# ColorControl.net
KiCad netlist of a schematic drawn in EAGLE
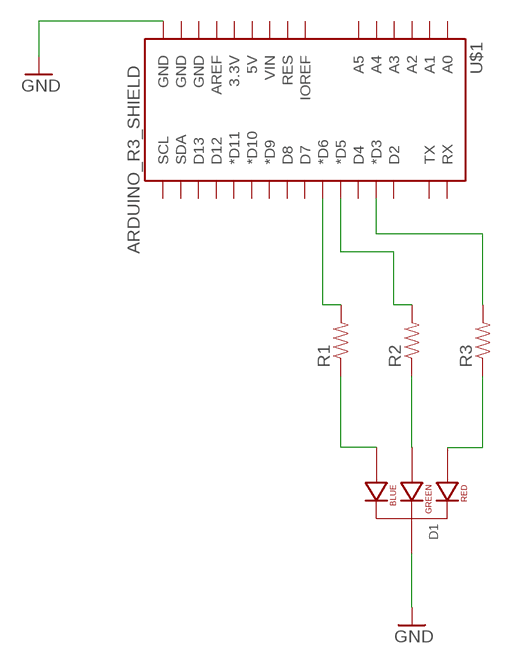
[diagram p0: schematic, sheet 1]

(export (version "E")
  (design (tool "Eeschema 10.0.6"))
  (components
    (comp (ref "D1")
      (value "LED-RGB-CC-THRUCLEAR")
      (footprint "eagle-import:LED-RGB-THRU")
      (libsource (lib "eagle-import") (part "LED-RGB-CC-THRUCLEAR"))
    )
    (comp (ref "R1")
      (value "RESISTORAXIAL-0.3")
      (footprint "eagle-import:AXIAL-0.3")
      (libsource (lib "eagle-import") (part "RESISTORAXIAL-0.3"))
    )
    (comp (ref "R2")
      (value "RESISTORAXIAL-0.3")
      (footprint "eagle-import:AXIAL-0.3")
      (libsource (lib "eagle-import") (part "RESISTORAXIAL-0.3"))
    )
    (comp (ref "R3")
      (value "RESISTORAXIAL-0.3")
      (footprint "eagle-import:AXIAL-0.3")
      (libsource (lib "eagle-import") (part "RESISTORAXIAL-0.3"))
    )
    (comp (ref "U$1")
      (value "ARDUINO_R3_SHIELD")
      (footprint "eagle-import:UNO_R3_SHIELD")
      (libsource (lib "eagle-import") (part "ARDUINO_R3_SHIELD"))
    )
  )
  (nets
    (net (code "1") (name "GND") (class "Default")
      (node (ref "D1") (pin "2") (pinfunction "CATHODE_2") (pintype "bidirectional"))
      (node (ref "U$1") (pin "GND@0") (pinfunction "GND_GND@0") (pintype "bidirectional"))
    )
    (net (code "2") (name "Net-(D1-BLUE_CATHODE)") (class "Default")
      (node (ref "D1") (pin "4") (pinfunction "BLUE_CATHODE_4") (pintype "bidirectional"))
      (node (ref "R1") (pin "P$1") (pinfunction "1_P$1") (pintype "passive"))
    )
    (net (code "3") (name "Net-(D1-GREEN_CATHODE)") (class "Default")
      (node (ref "D1") (pin "3") (pinfunction "GREEN_CATHODE_3") (pintype "bidirectional"))
      (node (ref "R2") (pin "P$1") (pinfunction "1_P$1") (pintype "passive"))
    )
    (net (code "4") (name "Net-(D1-RED_CATHODE)") (class "Default")
      (node (ref "D1") (pin "1") (pinfunction "RED_CATHODE_1") (pintype "bidirectional"))
      (node (ref "R3") (pin "P$1") (pinfunction "1_P$1") (pintype "passive"))
    )
    (net (code "5") (name "Net-(R1-2)") (class "Default")
      (node (ref "R1") (pin "P$2") (pinfunction "2_P$2") (pintype "passive"))
      (node (ref "U$1") (pin "D6") (pinfunction "*D6_D6") (pintype "bidirectional"))
    )
    (net (code "6") (name "Net-(R2-2)") (class "Default")
      (node (ref "R2") (pin "P$2") (pinfunction "2_P$2") (pintype "passive"))
      (node (ref "U$1") (pin "D5") (pinfunction "*D5_D5") (pintype "bidirectional"))
    )
    (net (code "7") (name "Net-(R3-2)") (class "Default")
      (node (ref "R3") (pin "P$2") (pinfunction "2_P$2") (pintype "passive"))
      (node (ref "U$1") (pin "D3") (pinfunction "*D3_D3") (pintype "bidirectional"))
    )
    (net (code "8") (name "unconnected-(U$1-*D9-PadD9)") (class "Default")
      (node (ref "U$1") (pin "D9") (pinfunction "*D9_D9") (pintype "bidirectional"))
    )
    (net (code "9") (name "unconnected-(U$1-*D10-PadD10)") (class "Default")
      (node (ref "U$1") (pin "D10") (pinfunction "*D10_D10") (pintype "bidirectional"))
    )
    (net (code "10") (name "unconnected-(U$1-*D11-PadD11)") (class "Default")
      (node (ref "U$1") (pin "D11") (pinfunction "*D11_D11") (pintype "bidirectional"))
    )
    (net (code "11") (name "unconnected-(U$1-GND-PadGND@1)") (class "Default")
      (node (ref "U$1") (pin "GND@1") (pinfunction "GND_GND@1") (pintype "bidirectional"))
    )
    (net (code "12") (name "unconnected-(U$1-GND-PadGND@2)") (class "Default")
      (node (ref "U$1") (pin "GND@2") (pinfunction "GND_GND@2") (pintype "bidirectional"))
    )
    (net (code "13") (name "unconnected-(U$1-Pad3.3V)") (class "Default")
      (node (ref "U$1") (pin "3.3V") (pinfunction "3.3V_3.3V") (pintype "bidirectional"))
    )
    (net (code "14") (name "unconnected-(U$1-Pad5V)") (class "Default")
      (node (ref "U$1") (pin "5V") (pinfunction "5V_5V") (pintype "bidirectional"))
    )
    (net (code "15") (name "unconnected-(U$1-PadA0)") (class "Default")
      (node (ref "U$1") (pin "A0") (pinfunction "A0_A0") (pintype "bidirectional"))
    )
    (net (code "16") (name "unconnected-(U$1-PadA1)") (class "Default")
      (node (ref "U$1") (pin "A1") (pinfunction "A1_A1") (pintype "bidirectional"))
    )
    (net (code "17") (name "unconnected-(U$1-PadA2)") (class "Default")
      (node (ref "U$1") (pin "A2") (pinfunction "A2_A2") (pintype "bidirectional"))
    )
    (net (code "18") (name "unconnected-(U$1-PadA3)") (class "Default")
      (node (ref "U$1") (pin "A3") (pinfunction "A3_A3") (pintype "bidirectional"))
    )
    (net (code "19") (name "unconnected-(U$1-PadA4)") (class "Default")
      (node (ref "U$1") (pin "A4") (pinfunction "A4_A4") (pintype "bidirectional"))
    )
    (net (code "20") (name "unconnected-(U$1-PadA5)") (class "Default")
      (node (ref "U$1") (pin "A5") (pinfunction "A5_A5") (pintype "bidirectional"))
    )
    (net (code "21") (name "unconnected-(U$1-PadAREF)") (class "Default")
      (node (ref "U$1") (pin "AREF") (pinfunction "AREF_AREF") (pintype "bidirectional"))
    )
    (net (code "22") (name "unconnected-(U$1-PadD2)") (class "Default")
      (node (ref "U$1") (pin "D2") (pinfunction "D2_D2") (pintype "bidirectional"))
    )
    (net (code "23") (name "unconnected-(U$1-PadD4)") (class "Default")
      (node (ref "U$1") (pin "D4") (pinfunction "D4_D4") (pintype "bidirectional"))
    )
    (net (code "24") (name "unconnected-(U$1-PadD7)") (class "Default")
      (node (ref "U$1") (pin "D7") (pinfunction "D7_D7") (pintype "bidirectional"))
    )
    (net (code "25") (name "unconnected-(U$1-PadD8)") (class "Default")
      (node (ref "U$1") (pin "D8") (pinfunction "D8_D8") (pintype "bidirectional"))
    )
    (net (code "26") (name "unconnected-(U$1-PadD12)") (class "Default")
      (node (ref "U$1") (pin "D12") (pinfunction "D12_D12") (pintype "bidirectional"))
    )
    (net (code "27") (name "unconnected-(U$1-PadD13)") (class "Default")
      (node (ref "U$1") (pin "D13") (pinfunction "D13_D13") (pintype "bidirectional"))
    )
    (net (code "28") (name "unconnected-(U$1-PadIOREF)") (class "Default")
      (node (ref "U$1") (pin "IOREF") (pinfunction "IOREF_IOREF") (pintype "bidirectional"))
    )
    (net (code "29") (name "unconnected-(U$1-PadRES)") (class "Default")
      (node (ref "U$1") (pin "RES") (pinfunction "RES_RES") (pintype "bidirectional"))
    )
    (net (code "30") (name "unconnected-(U$1-PadRX)") (class "Default")
      (node (ref "U$1") (pin "RX") (pinfunction "RX_RX") (pintype "bidirectional"))
    )
    (net (code "31") (name "unconnected-(U$1-PadSCL)") (class "Default")
      (node (ref "U$1") (pin "SCL") (pinfunction "SCL_SCL") (pintype "bidirectional"))
    )
    (net (code "32") (name "unconnected-(U$1-PadSDA)") (class "Default")
      (node (ref "U$1") (pin "SDA") (pinfunction "SDA_SDA") (pintype "bidirectional"))
    )
    (net (code "33") (name "unconnected-(U$1-PadTX)") (class "Default")
      (node (ref "U$1") (pin "TX") (pinfunction "TX_TX") (pintype "bidirectional"))
    )
    (net (code "34") (name "unconnected-(U$1-PadVIN)") (class "Default")
      (node (ref "U$1") (pin "VIN") (pinfunction "VIN_VIN") (pintype "bidirectional"))
    )
  )
)
